# 02-AD9546_StrapsXtal.net
KiCad netlist of a schematic drawn in Altium Designer
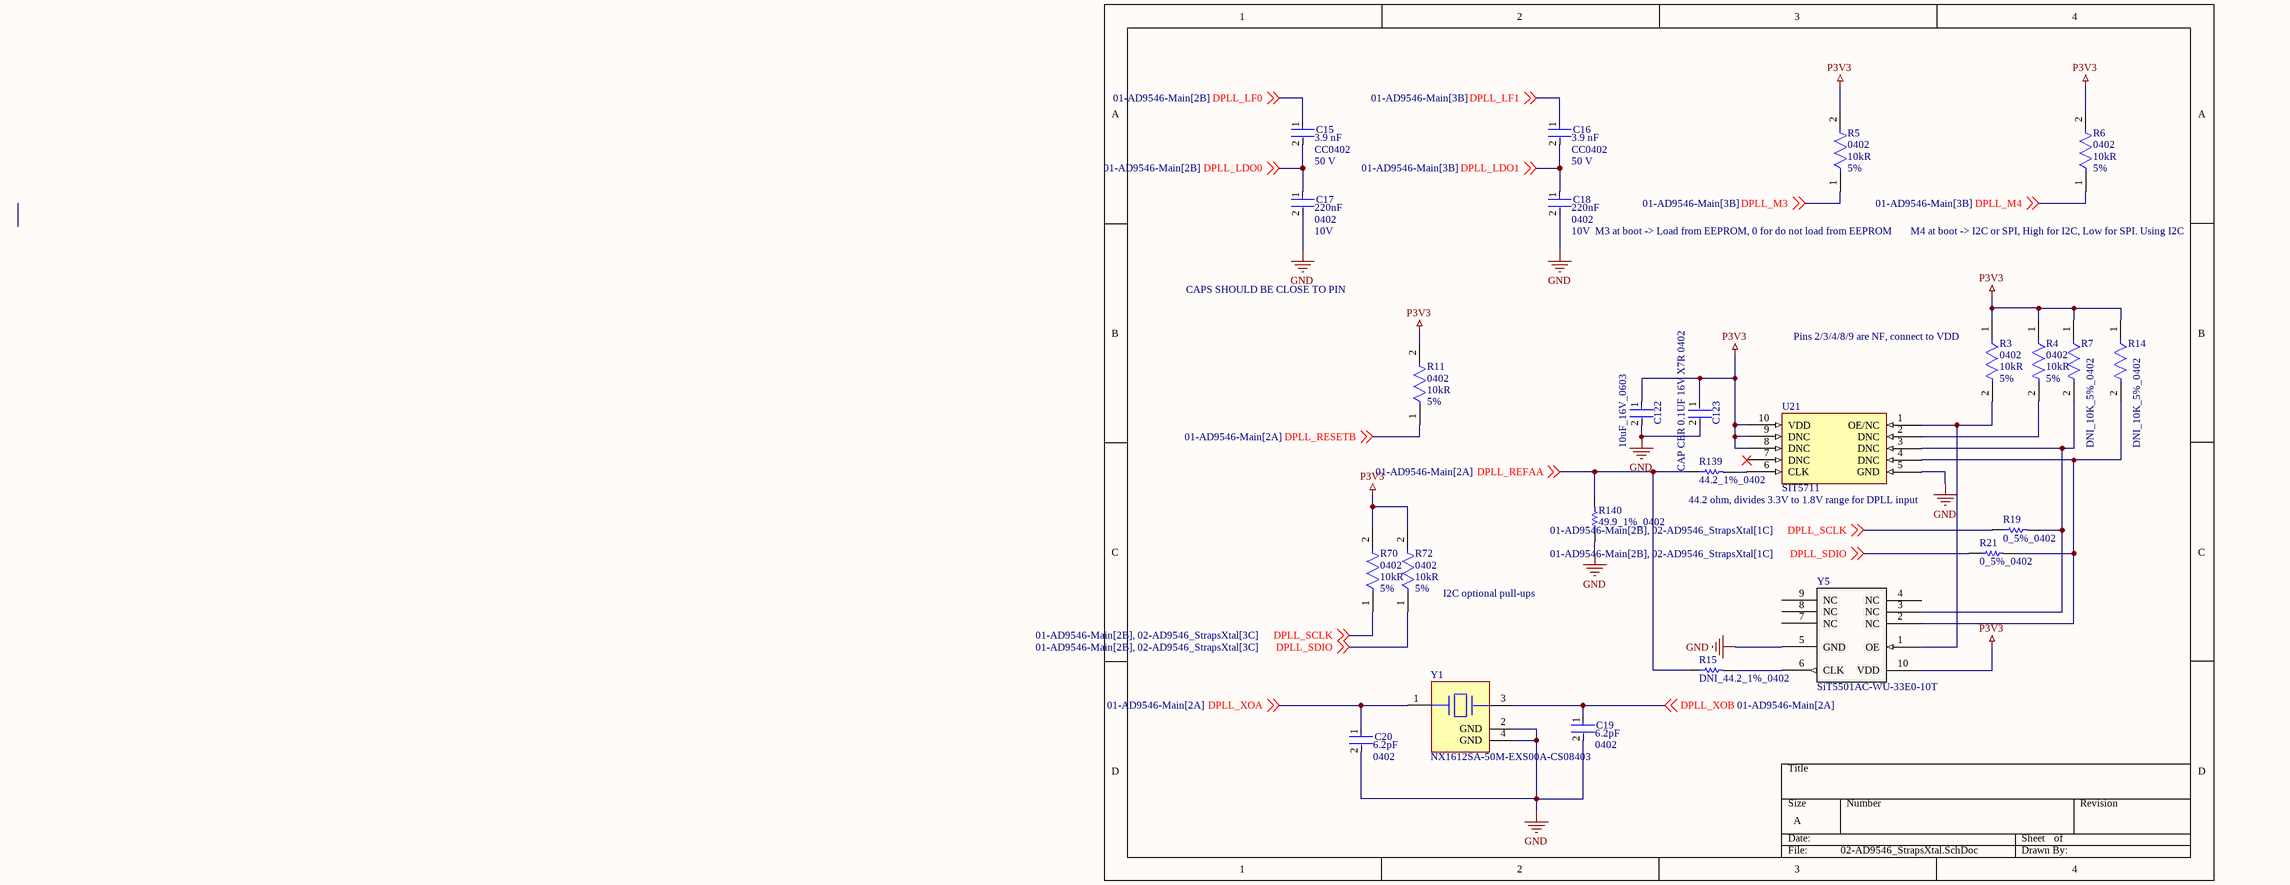
[diagram p0: 02-AD9546_StrapsXtal.SchDoc]

(export (version "E")
  (design (tool "Eeschema 10.0.6"))
  (components
    (comp (ref "C15")
      (value "3.9 nF")
      (footprint "FP-CC0402-MFG")
      (description "CAP CER 3900PF 50V X7R 0402")
      (fields
        (field (name "OCTOPART") "https://octopart.com/cc0402krx7r9bb392-yageo-9291741")
        (field (name "TOLERANCE") "0.1")
        (field (name "VOLTAGE RATING") "50 V")
        (field (name "PACKAGE") "CC0402")
      )
      (libsource (lib "Altium Content Vault") (part "11868f565c42a9108669ba33697ecf6"))
    )
    (comp (ref "C16")
      (value "3.9 nF")
      (footprint "FP-CC0402-MFG")
      (description "CAP CER 3900PF 50V X7R 0402")
      (fields
        (field (name "OCTOPART") "https://octopart.com/cc0402krx7r9bb392-yageo-9291741")
        (field (name "TOLERANCE") "0.1")
        (field (name "VOLTAGE RATING") "50 V")
        (field (name "PACKAGE") "CC0402")
      )
      (libsource (lib "Altium Content Vault") (part "11868f565c42a9108669ba33697ecf6"))
    )
    (comp (ref "C17")
      (value "GRM155R61A224KE19D")
      (footprint "FP-GRM155-0_05-IPC_A")
      (description "CAP CER 0.22UF 10V X5R 0402")
      (fields
        (field (name "VOLTAGE") "10V")
        (field (name "TOLERANCE") "10%")
        (field (name "CASE/PACKAGE") "0402")
        (field (name "CAPACITANCE") "220nF")
      )
      (libsource (lib "Altium Content Vault") (part "02cd4be3c70576c341d710602a673aa"))
    )
    (comp (ref "C18")
      (value "GRM155R61A224KE19D")
      (footprint "FP-GRM155-0_05-IPC_A")
      (description "CAP CER 0.22UF 10V X5R 0402")
      (fields
        (field (name "VOLTAGE") "10V")
        (field (name "TOLERANCE") "10%")
        (field (name "CASE/PACKAGE") "0402")
        (field (name "CAPACITANCE") "220nF")
      )
      (libsource (lib "Altium Content Vault") (part "02cd4be3c70576c341d710602a673aa"))
    )
    (comp (ref "C19")
      (value "CL05C6R2CB5NNNC")
      (footprint "FP-CL468-IPC_C")
      (description "Cap Ceramic 6.2pF 50V C0G ±0.25pF SMD 0402 +125°C Paper T/R")
      (fields (field (name "CASE/PACKAGE") "0402") (field (name "CAPACITANCE") "6.2pF"))
      (libsource (lib "Altium Content Vault") (part "b4654b650e69147ec39a6b967a45e02"))
    )
    (comp (ref "C20")
      (value "CL05C6R2CB5NNNC")
      (footprint "FP-CL468-IPC_C")
      (description "Cap Ceramic 6.2pF 50V C0G ±0.25pF SMD 0402 +125°C Paper T/R")
      (fields (field (name "CASE/PACKAGE") "0402") (field (name "CAPACITANCE") "6.2pF"))
      (libsource (lib "Altium Content Vault") (part "b4654b650e69147ec39a6b967a45e02"))
    )
    (comp (ref "C122")
      (value "10uF_16V_0603")
      (footprint "FP-C1608-MFG")
      (description "CAP CER 10UF 16V X5R 0603")
      (fields
        (field (name "OCTOPART") "https://octopart.com/c1608x5r1c106m080ab-tdk-26013480")
        (field (name "MANUFACTURER") "TDK Corporation")
      )
      (libsource (lib "Altium Content Vault") (part "11868f565c42a9108669ba33697ecf6"))
    )
    (comp (ref "C123")
      (value "GRM155R71C104KA88D")
      (footprint "FP-GRM15-MFG")
      (description "CAP CER 0.1UF 16V X7R 0402")
      (fields
        (field (name "TOLERANCE") "10%")
        (field (name "OCTOPART") "https://octopart.com/grm155r71c104ka88d-murata-196880")
        (field (name "DIGIKEY DESCRIPTION") "CAP CER 0.1UF 16V X7R 0402")
      )
      (libsource (lib "Altium Content Vault") (part "236180d848d6139a670b325ea6854c9"))
    )
    (comp (ref "R3")
      (value "CRCW040210K0JNED")
      (footprint "FP-CRCW0402-e3-IPC_B")
      (description "RES Thick Film, 10kΩ, 5%, 0.063W, 200ppm/°C, 0402")
      (fields
        (field (name "CASE/PACKAGE") "0402")
        (field (name "RESISTANCE") "10kR")
        (field (name "TOLERANCE") "5%")
      )
      (libsource (lib "Altium Content Vault") (part "1029c3af85768c4190bb7ad29bc67b5"))
    )
    (comp (ref "R4")
      (value "CRCW040210K0JNED")
      (footprint "FP-CRCW0402-e3-IPC_B")
      (description "RES Thick Film, 10kΩ, 5%, 0.063W, 200ppm/°C, 0402")
      (fields
        (field (name "CASE/PACKAGE") "0402")
        (field (name "RESISTANCE") "10kR")
        (field (name "TOLERANCE") "5%")
      )
      (libsource (lib "Altium Content Vault") (part "1029c3af85768c4190bb7ad29bc67b5"))
    )
    (comp (ref "R5")
      (value "CRCW040210K0JNED")
      (footprint "FP-CRCW0402-e3-IPC_B")
      (description "RES Thick Film, 10kΩ, 5%, 0.063W, 200ppm/°C, 0402")
      (fields
        (field (name "CASE/PACKAGE") "0402")
        (field (name "RESISTANCE") "10kR")
        (field (name "TOLERANCE") "5%")
      )
      (libsource (lib "Altium Content Vault") (part "1029c3af85768c4190bb7ad29bc67b5"))
    )
    (comp (ref "R6")
      (value "CRCW040210K0JNED")
      (footprint "FP-CRCW0402-e3-IPC_B")
      (description "RES Thick Film, 10kΩ, 5%, 0.063W, 200ppm/°C, 0402")
      (fields
        (field (name "CASE/PACKAGE") "0402")
        (field (name "RESISTANCE") "10kR")
        (field (name "TOLERANCE") "5%")
      )
      (libsource (lib "Altium Content Vault") (part "1029c3af85768c4190bb7ad29bc67b5"))
    )
    (comp (ref "R7")
      (value "DNI_10K_5%_0402")
      (footprint "FP-CRCW0402-e3-IPC_B")
      (description "RES Thick Film, 10kΩ, 5%, 0.063W, 200ppm/°C, 0402")
      (fields (field (name "TOLERANCE") "5%"))
      (libsource (lib "Altium Content Vault") (part "1029c3af85768c4190bb7ad29bc67b5"))
    )
    (comp (ref "R11")
      (value "CRCW040210K0JNED")
      (footprint "FP-CRCW0402-e3-IPC_B")
      (description "RES Thick Film, 10kΩ, 5%, 0.063W, 200ppm/°C, 0402")
      (fields
        (field (name "CASE/PACKAGE") "0402")
        (field (name "RESISTANCE") "10kR")
        (field (name "TOLERANCE") "5%")
      )
      (libsource (lib "Altium Content Vault") (part "1029c3af85768c4190bb7ad29bc67b5"))
    )
    (comp (ref "R14")
      (value "DNI_10K_5%_0402")
      (footprint "FP-CRCW0402-e3-IPC_B")
      (description "RES Thick Film, 10kΩ, 5%, 0.063W, 200ppm/°C, 0402")
      (fields (field (name "TOLERANCE") "5%"))
      (libsource (lib "Altium Content Vault") (part "1029c3af85768c4190bb7ad29bc67b5"))
    )
    (comp (ref "R15")
      (value "DNI_44.2_1%_0402")
      (footprint "RESC0402(1005)_M")
      (description "44R2 0.063W 1% 0402 (1005 Metric)  SMD")
      (fields (field (name "TOLERANCE") "1 %") (field (name "POWER") "0.063 W"))
      (libsource (lib "Altium Content Vault") (part "RES"))
    )
    (comp (ref "R19")
      (value "0_5%_0402")
      (footprint "RESC1005X40X25NL05T10")
      (fields (field (name "MANUFACTURER") "Yageo / Phycomp") (field (name "PART NUMBER") "RC0402JR-070RL"))
      (libsource (lib "Altium Content Vault") (part "RES"))
    )
    (comp (ref "R21")
      (value "0_5%_0402")
      (footprint "RESC1005X40X25NL05T10")
      (fields (field (name "MANUFACTURER") "Yageo / Phycomp") (field (name "PART NUMBER") "RC0402JR-070RL"))
      (libsource (lib "Altium Content Vault") (part "RES"))
    )
    (comp (ref "R70")
      (value "CRCW040210K0JNED")
      (footprint "FP-CRCW0402-e3-IPC_B")
      (description "RES Thick Film, 10kΩ, 5%, 0.063W, 200ppm/°C, 0402")
      (fields
        (field (name "CASE/PACKAGE") "0402")
        (field (name "RESISTANCE") "10kR")
        (field (name "TOLERANCE") "5%")
      )
      (libsource (lib "Altium Content Vault") (part "1029c3af85768c4190bb7ad29bc67b5"))
    )
    (comp (ref "R72")
      (value "CRCW040210K0JNED")
      (footprint "FP-CRCW0402-e3-IPC_B")
      (description "RES Thick Film, 10kΩ, 5%, 0.063W, 200ppm/°C, 0402")
      (fields
        (field (name "CASE/PACKAGE") "0402")
        (field (name "RESISTANCE") "10kR")
        (field (name "TOLERANCE") "5%")
      )
      (libsource (lib "Altium Content Vault") (part "1029c3af85768c4190bb7ad29bc67b5"))
    )
    (comp (ref "R139")
      (value "44.2_1%_0402")
      (footprint "RESC0402(1005)_M")
      (description "44R2 0.063W 1% 0402 (1005 Metric)  SMD")
      (fields (field (name "TOLERANCE") "1 %") (field (name "POWER") "0.063 W"))
      (libsource (lib "Altium Content Vault") (part "RES"))
    )
    (comp (ref "R140")
      (value "49.9_1%_0402")
      (footprint "RESC1005X40X25NL05T05")
      (fields (field (name "MANUFACTURER") "Panasonic") (field (name "PART NUMBER") "ERJ-2RKF49R9X"))
      (libsource (lib "Altium Content Vault") (part "RES"))
    )
    (comp (ref "U21")
      (value "SIT5711")
      (footprint "SIT5711")
      (libsource (lib "TimeDrive_Lib") (part "SIT5711"))
    )
    (comp (ref "Y1")
      (value "NX1612SA-50M-EXS00A-CS08403")
      (footprint "FP-NX1612SA-MFG")
      (description "CRYSTAL 50MHZ 8PF SMD")
      (libsource (lib "Altium Content Vault") (part "53a0930ab107b8af0dbb63ba5da429b"))
    )
    (comp (ref "Y5")
      (value "SiTime_SiT5501AC-WU-33E0-10T")
      (footprint "SITIME_SPL-086-CQFN-010-C07050_REV_DRAFT")
      (description "OSC, MEMS, STRATUM 3E, 10.000MHZ, 10PPB STAB, LVCMOS, 3.3V, O/P EN, 7.0X5.0X2.2MM, CQFN-10")
      (fields
        (field (name "MANUFACTURER PART NUMBER") "SiT5501AC-WU-33E0-10T")
        (field (name "INTERNAL PART NUMBER") "820-00386-00")
        (field (name "MANUFACTURER") "SiTime")
      )
      (libsource (lib "Meta RLR Altium Enterprise Server") (part "SiT5501AC-WU-33E0-10T_010pin"))
    )
  )
  (nets
    (net (code "1") (name "DPLL_LDO0") (class "Default")
      (node (ref "C15") (pin "2") (pinfunction "2_2") (pintype "passive"))
      (node (ref "C17") (pin "1") (pinfunction "1_1") (pintype "passive"))
    )
    (net (code "2") (name "DPLL_LDO1") (class "Default")
      (node (ref "C16") (pin "2") (pinfunction "2_2") (pintype "passive"))
      (node (ref "C18") (pin "1") (pinfunction "1_1") (pintype "passive"))
    )
    (net (code "3") (name "DPLL_LF0") (class "Default")
      (node (ref "C15") (pin "1") (pinfunction "1_1") (pintype "passive"))
    )
    (net (code "4") (name "DPLL_LF1") (class "Default")
      (node (ref "C16") (pin "1") (pinfunction "1_1") (pintype "passive"))
    )
    (net (code "5") (name "DPLL_M3") (class "Default")
      (node (ref "R5") (pin "1") (pinfunction "1_1") (pintype "passive"))
    )
    (net (code "6") (name "DPLL_M4") (class "Default")
      (node (ref "R6") (pin "1") (pinfunction "1_1") (pintype "passive"))
    )
    (net (code "7") (name "DPLL_REFAA") (class "Default")
      (node (ref "R139") (pin "1") (pinfunction "1_1") (pintype "passive"))
      (node (ref "R140") (pin "2") (pinfunction "2_2") (pintype "passive"))
      (node (ref "R15") (pin "1") (pinfunction "1_1") (pintype "passive"))
    )
    (net (code "8") (name "DPLL_RESETB") (class "Default")
      (node (ref "R11") (pin "1") (pinfunction "1_1") (pintype "passive"))
    )
    (net (code "9") (name "DPLL_SCLK") (class "Default")
      (node (ref "R19") (pin "1") (pinfunction "1_1") (pintype "passive"))
      (node (ref "R70") (pin "1") (pinfunction "1_1") (pintype "passive"))
    )
    (net (code "10") (name "DPLL_SDIO") (class "Default")
      (node (ref "R21") (pin "1") (pinfunction "1_1") (pintype "passive"))
      (node (ref "R72") (pin "1") (pinfunction "1_1") (pintype "passive"))
    )
    (net (code "11") (name "DPLL_XOA") (class "Default")
      (node (ref "C20") (pin "1") (pinfunction "1_1") (pintype "passive"))
      (node (ref "Y1") (pin "1") (pinfunction "1_Xtal_1") (pintype "passive"))
    )
    (net (code "12") (name "DPLL_XOB") (class "Default")
      (node (ref "C19") (pin "1") (pinfunction "1_1") (pintype "passive"))
      (node (ref "Y1") (pin "3") (pinfunction "2_Xtal_3") (pintype "passive"))
    )
    (net (code "13") (name "GND") (class "Default")
      (node (ref "C122") (pin "2") (pinfunction "2_2") (pintype "passive"))
      (node (ref "C123") (pin "2") (pinfunction "2_2") (pintype "passive"))
      (node (ref "C17") (pin "2") (pinfunction "2_2") (pintype "passive"))
      (node (ref "C18") (pin "2") (pinfunction "2_2") (pintype "passive"))
      (node (ref "C19") (pin "2") (pinfunction "2_2") (pintype "passive"))
      (node (ref "C20") (pin "2") (pinfunction "2_2") (pintype "passive"))
      (node (ref "R140") (pin "1") (pinfunction "1_1") (pintype "passive"))
      (node (ref "U21") (pin "5") (pinfunction "GND_5") (pintype "input"))
      (node (ref "Y1") (pin "2") (pinfunction "GND_2") (pintype "power_in"))
      (node (ref "Y1") (pin "4") (pinfunction "GND_4") (pintype "power_in"))
      (node (ref "Y5") (pin "5") (pinfunction "GND_5") (pintype "power_in"))
    )
    (net (code "14") (name "Net-(R4-Pad2)") (class "Default")
      (node (ref "R4") (pin "2") (pinfunction "2_2") (pintype "passive"))
      (node (ref "U21") (pin "2") (pinfunction "DNC_2") (pintype "input"))
    )
    (net (code "15") (name "Net-(R14-Pad2)") (class "Default")
      (node (ref "R14") (pin "2") (pinfunction "2_2") (pintype "passive"))
      (node (ref "R21") (pin "2") (pinfunction "2_2") (pintype "passive"))
      (node (ref "U21") (pin "4") (pinfunction "DNC_4") (pintype "input"))
      (node (ref "Y5") (pin "2") (pinfunction "NC_2") (pintype "passive"))
    )
    (net (code "16") (name "Net-(R19-Pad2)") (class "Default")
      (node (ref "R19") (pin "2") (pinfunction "2_2") (pintype "passive"))
      (node (ref "R7") (pin "2") (pinfunction "2_2") (pintype "passive"))
      (node (ref "U21") (pin "3") (pinfunction "DNC_3") (pintype "input"))
      (node (ref "Y5") (pin "3") (pinfunction "NC_3") (pintype "passive"))
    )
    (net (code "17") (name "Net-(U21-CLK)") (class "Default")
      (node (ref "R139") (pin "2") (pinfunction "2_2") (pintype "passive"))
      (node (ref "U21") (pin "6") (pinfunction "CLK_6") (pintype "input"))
    )
    (net (code "18") (name "Net-(U21-OE{slash}NC)") (class "Default")
      (node (ref "R3") (pin "2") (pinfunction "2_2") (pintype "passive"))
      (node (ref "U21") (pin "1") (pinfunction "OE/NC_1") (pintype "input"))
      (node (ref "Y5") (pin "1") (pinfunction "OE_1") (pintype "input"))
    )
    (net (code "19") (name "Net-(Y5-CLK)") (class "Default")
      (node (ref "R15") (pin "2") (pinfunction "2_2") (pintype "passive"))
      (node (ref "Y5") (pin "6") (pinfunction "CLK_6") (pintype "output"))
    )
    (net (code "20") (name "P3V3") (class "Default")
      (node (ref "C122") (pin "1") (pinfunction "1_1") (pintype "passive"))
      (node (ref "C123") (pin "1") (pinfunction "1_1") (pintype "passive"))
      (node (ref "R11") (pin "2") (pinfunction "2_2") (pintype "passive"))
      (node (ref "R14") (pin "1") (pinfunction "1_1") (pintype "passive"))
      (node (ref "R3") (pin "1") (pinfunction "1_1") (pintype "passive"))
      (node (ref "R4") (pin "1") (pinfunction "1_1") (pintype "passive"))
      (node (ref "R5") (pin "2") (pinfunction "2_2") (pintype "passive"))
      (node (ref "R6") (pin "2") (pinfunction "2_2") (pintype "passive"))
      (node (ref "R7") (pin "1") (pinfunction "1_1") (pintype "passive"))
      (node (ref "R70") (pin "2") (pinfunction "2_2") (pintype "passive"))
      (node (ref "R72") (pin "2") (pinfunction "2_2") (pintype "passive"))
      (node (ref "U21") (pin "10") (pinfunction "VDD_10") (pintype "input"))
      (node (ref "U21") (pin "8") (pinfunction "DNC_8") (pintype "input"))
      (node (ref "U21") (pin "9") (pinfunction "DNC_9") (pintype "input"))
      (node (ref "Y5") (pin "10") (pinfunction "VDD_10") (pintype "power_in"))
    )
    (net (code "21") (name "unconnected-(U21-DNC-Pad7)") (class "Default")
      (node (ref "U21") (pin "7") (pinfunction "DNC_7") (pintype "input+no_connect"))
    )
    (net (code "22") (name "unconnected-(Y5-NC-Pad4)") (class "Default")
      (node (ref "Y5") (pin "4") (pinfunction "NC_4") (pintype "passive"))
    )
    (net (code "23") (name "unconnected-(Y5-NC-Pad7)") (class "Default")
      (node (ref "Y5") (pin "7") (pinfunction "NC_7") (pintype "passive"))
    )
    (net (code "24") (name "unconnected-(Y5-NC-Pad8)") (class "Default")
      (node (ref "Y5") (pin "8") (pinfunction "NC_8") (pintype "passive"))
    )
    (net (code "25") (name "unconnected-(Y5-NC-Pad9)") (class "Default")
      (node (ref "Y5") (pin "9") (pinfunction "NC_9") (pintype "passive"))
    )
  )
)
